# RTC_TEMP.net
KiCad netlist of a schematic drawn in Altium Designer
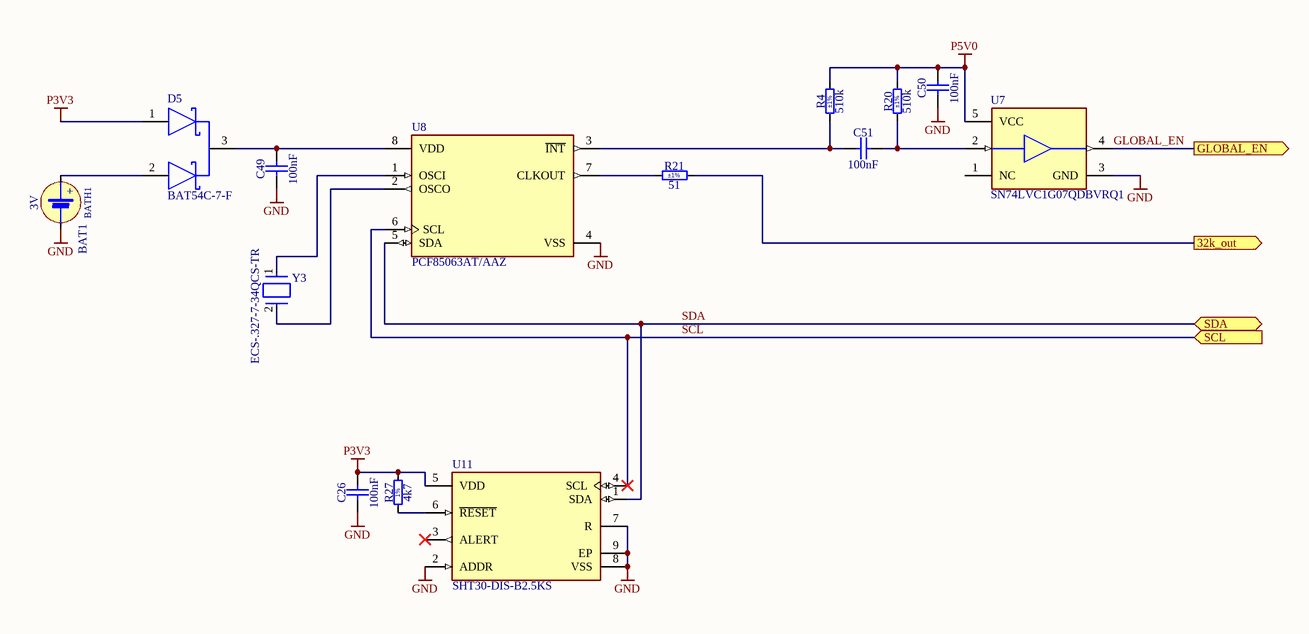
[diagram p0: RTC_TEMP.SchDoc]

(export (version "E")
  (design (tool "Eeschema 10.0.6"))
  (components
    (comp (ref "BAT1")
      (value "3V")
      (footprint "BAT_VARTA_CR1220")
      (description "Battery for use only with Socket Holder")
      (fields
        (field (name "PART NUMBER") "BAT_VARTA_CR1220")
        (field (name "POWER") "35mAh")
        (field (name "AUTHOR") "CERN DEM JLC")
      )
      (libsource (lib "Eletro-mechanical") (part "Battery No Pin"))
    )
    (comp (ref "BATH1")
      (value "~")
      (footprint "BATH_KEYSTONE_3000")
      (description "Battery Holder whit 2 Pin")
      (fields
        (field (name "PART NUMBER") "BATH_KEYSTONE_3000")
        (field (name "MANUFACTURER") "KEYSTONE")
        (field (name "AUTHOR") "CERN DEM JLC")
      )
      (libsource (lib "Eletro-mechanical") (part "Battery Holder 2 Pin"))
    )
    (comp (ref "C26")
      (value "100nF")
      (footprint "CAPC1005X55N")
      (description "Non-polarised capacitor")
      (fields
        (field (name "MANUFACTURER PART NUMBER") "CC0402_100NF_16V_10%_X5R")
        (field (name "MANUFACTURER") "GENERIC")
        (field (name "AUTHOR") "CERN DEM JLC")
      )
      (libsource (lib "Capacitors") (part "Capacitor - non polarized"))
    )
    (comp (ref "C49")
      (value "100nF")
      (footprint "CAPC1005X55N")
      (description "Non-polarised capacitor")
      (fields
        (field (name "MANUFACTURER PART NUMBER") "CC0402_100NF_16V_10%_X5R")
        (field (name "MANUFACTURER") "GENERIC")
        (field (name "AUTHOR") "CERN DEM JLC")
      )
      (libsource (lib "Capacitors") (part "Capacitor - non polarized"))
    )
    (comp (ref "C50")
      (value "100nF")
      (footprint "CAPC1005X55N")
      (description "Non-polarised capacitor")
      (fields
        (field (name "MANUFACTURER PART NUMBER") "CC0402_100NF_16V_10%_X5R")
        (field (name "MANUFACTURER") "GENERIC")
        (field (name "AUTHOR") "CERN DEM JLC")
      )
      (libsource (lib "Capacitors") (part "Capacitor - non polarized"))
    )
    (comp (ref "C51")
      (value "100nF")
      (footprint "CAPC1005X55N")
      (description "Non-polarised capacitor")
      (fields
        (field (name "MANUFACTURER PART NUMBER") "CC0402_100NF_16V_10%_X5R")
        (field (name "MANUFACTURER") "GENERIC")
        (field (name "AUTHOR") "CERN DEM JLC")
      )
      (libsource (lib "Capacitors") (part "Capacitor - non polarized"))
    )
    (comp (ref "D5")
      (value "BAT54C-7-F")
      (footprint "FP-SOT23-IPC_A")
      (description "DIODE ARRAY SCHOTTKY 30V SOT23-3")
      (libsource (lib "Altium Content Vault") (part "3eac2aa0c1ac86323ecc23460aa29c6"))
    )
    (comp (ref "R4")
      (value "510k")
      (footprint "RESC1005X40N")
      (description "Resistor - 1%")
      (fields
        (field (name "TOLERANCE") "±1%")
        (field (name "PART NUMBER") "R0402_510K_1%_0.0625W_100PPM")
        (field (name "POWER") "0.0625W")
        (field (name "AUTHOR") "CERN DEM JLC")
      )
      (libsource (lib "Resistors") (part "Resistor - 1%"))
    )
    (comp (ref "R20")
      (value "510k")
      (footprint "RESC1005X40N")
      (description "Resistor - 1%")
      (fields
        (field (name "TOLERANCE") "±1%")
        (field (name "PART NUMBER") "R0402_510K_1%_0.0625W_100PPM")
        (field (name "POWER") "0.0625W")
        (field (name "AUTHOR") "CERN DEM JLC")
      )
      (libsource (lib "Resistors") (part "Resistor - 1%"))
    )
    (comp (ref "R21")
      (value "51")
      (footprint "RESC1005X40N")
      (description "Resistor - 1%")
      (fields
        (field (name "TOLERANCE") "±1%")
        (field (name "PART NUMBER") "R0402_51R_1%_0.0625W_100PPM")
        (field (name "POWER") "0.0625W")
        (field (name "AUTHOR") "CERN DEM JLC")
      )
      (libsource (lib "Resistors") (part "Resistor - 1%"))
    )
    (comp (ref "R27")
      (value "4k7")
      (footprint "RESC1005X40N")
      (description "Resistor - 1%")
      (fields
        (field (name "PART NUMBER") "R0402_4K7_1%_0.0625W_100PPM")
        (field (name "POWER") "0.0625W")
        (field (name "AUTHOR") "CERN DEM JLC")
      )
      (libsource (lib "Resistors") (part "Resistor - 1%"))
    )
    (comp (ref "U7")
      (value "SN74LVC1G07QDBVRQ1")
      (footprint "FP-DBV0005A-IPC_A")
      (description "IC BUF NON-INVERT 5.5V SOT23-5")
      (libsource (lib "Altium Content Vault") (part "fd2d5996bf727b2de8003b3fc962381"))
    )
    (comp (ref "U8")
      (value "PCF85063AT/AAZ")
      (footprint "FP-SOT96-1-MFG")
      (description "IC RTC CLK/CALENDAR I2C 8SOIC")
      (libsource (lib "Altium Content Vault") (part "4dc28abe8360043d43596dd8250e67d"))
    )
    (comp (ref "U11")
      (value "SHT30-DIS-B2.5KS")
      (footprint "FP-SHT30-DIS-B2_5KS-MFG")
      (description "SENSOR HUMID/TEMP 5V I2C 3% SMD")
      (libsource (lib "Altium Content Vault") (part "3a40f6fddac460f1c5fb2adec20f0f2"))
    )
    (comp (ref "Y3")
      (value "ECS-.327-7-34QCS-TR")
      (footprint "FP-ECX-34Q-0")
      (description "CRYSTAL 32.768KHZ 7PF SMD")
      (fields (field (name "TOLERANCE") "10ppm") (field (name "MANUFACTURER") "ECS Inc."))
      (libsource (lib "Altium Content Vault") (part "99724985039315a44fd0d1401b84e49"))
    )
  )
  (nets
    (net (code "1") (name "/32k_out") (class "Default")
      (node (ref "R21") (pin "2") (pinfunction "2_2") (pintype "passive"))
    )
    (net (code "2") (name "/GLOBAL_EN") (class "Default")
      (node (ref "U7") (pin "4") (pinfunction "Y_4") (pintype "output"))
    )
    (net (code "3") (name "/SCL") (class "Default")
      (node (ref "U11") (pin "4") (pinfunction "SCL_4") (pintype "bidirectional"))
      (node (ref "U8") (pin "6") (pinfunction "SCL_6") (pintype "input"))
    )
    (net (code "4") (name "/SDA") (class "Default")
      (node (ref "U11") (pin "1") (pinfunction "SDA_1") (pintype "bidirectional"))
      (node (ref "U8") (pin "5") (pinfunction "SDA_5") (pintype "bidirectional"))
    )
    (net (code "5") (name "GND") (class "Default")
      (node (ref "BATH1") (pin "2") (pinfunction "MINUS_2") (pintype "power_in"))
      (node (ref "C26") (pin "1") (pinfunction "1_1") (pintype "passive"))
      (node (ref "C49") (pin "1") (pinfunction "1_1") (pintype "passive"))
      (node (ref "C50") (pin "1") (pinfunction "1_1") (pintype "passive"))
      (node (ref "U11") (pin "2") (pinfunction "ADDR_2") (pintype "input"))
      (node (ref "U11") (pin "7") (pinfunction "R_7") (pintype "passive"))
      (node (ref "U11") (pin "8") (pinfunction "VSS_8") (pintype "power_in"))
      (node (ref "U11") (pin "9") (pinfunction "EP_9") (pintype "passive"))
      (node (ref "U7") (pin "3") (pinfunction "GND_3") (pintype "power_in"))
      (node (ref "U8") (pin "4") (pinfunction "VSS_4") (pintype "power_in"))
    )
    (net (code "6") (name "Net-(BATH1-PLUS)") (class "Default")
      (node (ref "BATH1") (pin "1") (pinfunction "PLUS_1") (pintype "power_in"))
      (node (ref "D5") (pin "2") (pinfunction "2_ANODE_2") (pintype "passive"))
    )
    (net (code "7") (name "Net-(D5-COMMON_CATHODE)") (class "Default")
      (node (ref "C49") (pin "2") (pinfunction "2_2") (pintype "passive"))
      (node (ref "D5") (pin "3") (pinfunction "COMMON_CATHODE_3") (pintype "passive"))
      (node (ref "U8") (pin "8") (pinfunction "VDD_8") (pintype "power_in"))
    )
    (net (code "8") (name "Net-(U7-A)") (class "Default")
      (node (ref "C51") (pin "2") (pinfunction "2_2") (pintype "passive"))
      (node (ref "R20") (pin "1") (pinfunction "1_1") (pintype "passive"))
      (node (ref "U7") (pin "2") (pinfunction "A_2") (pintype "input"))
    )
    (net (code "9") (name "Net-(U8-CLKOUT)") (class "Default")
      (node (ref "R21") (pin "1") (pinfunction "1_1") (pintype "passive"))
      (node (ref "U8") (pin "7") (pinfunction "CLKOUT_7") (pintype "output"))
    )
    (net (code "10") (name "Net-(U8-OSCI)") (class "Default")
      (node (ref "U8") (pin "1") (pinfunction "OSCI_1") (pintype "input"))
      (node (ref "Y3") (pin "1") (pinfunction "In/Out_1") (pintype "passive"))
    )
    (net (code "11") (name "Net-(U8-OSCO)") (class "Default")
      (node (ref "U8") (pin "2") (pinfunction "OSCO_2") (pintype "output"))
      (node (ref "Y3") (pin "2") (pinfunction "Out/In_2") (pintype "passive"))
    )
    (net (code "12") (name "Net-(U8-~{INT})") (class "Default")
      (node (ref "C51") (pin "1") (pinfunction "1_1") (pintype "passive"))
      (node (ref "R4") (pin "1") (pinfunction "1_1") (pintype "passive"))
      (node (ref "U8") (pin "3") (pinfunction "~{INT}_3") (pintype "output"))
    )
    (net (code "13") (name "Net-(U11-~{RESET})") (class "Default")
      (node (ref "R27") (pin "1") (pinfunction "1_1") (pintype "passive"))
      (node (ref "U11") (pin "6") (pinfunction "~{RESET}_6") (pintype "input"))
    )
    (net (code "14") (name "P3V3") (class "Default")
      (node (ref "C26") (pin "2") (pinfunction "2_2") (pintype "passive"))
      (node (ref "D5") (pin "1") (pinfunction "1_ANODE_1") (pintype "passive"))
      (node (ref "R27") (pin "2") (pinfunction "2_2") (pintype "passive"))
      (node (ref "U11") (pin "5") (pinfunction "VDD_5") (pintype "power_in"))
    )
    (net (code "15") (name "P5V0") (class "Default")
      (node (ref "C50") (pin "2") (pinfunction "2_2") (pintype "passive"))
      (node (ref "R20") (pin "2") (pinfunction "2_2") (pintype "passive"))
      (node (ref "R4") (pin "2") (pinfunction "2_2") (pintype "passive"))
      (node (ref "U7") (pin "5") (pinfunction "VCC_5") (pintype "power_in"))
    )
    (net (code "16") (name "unconnected-(U7-NC-Pad1)") (class "Default")
      (node (ref "U7") (pin "1") (pinfunction "NC_1") (pintype "passive"))
    )
    (net (code "17") (name "unconnected-(U11-ALERT-Pad3)") (class "Default")
      (node (ref "U11") (pin "3") (pinfunction "ALERT_3") (pintype "output+no_connect"))
    )
  )
)
